# RS485_junction.net
KiCad netlist of a schematic drawn in EAGLE
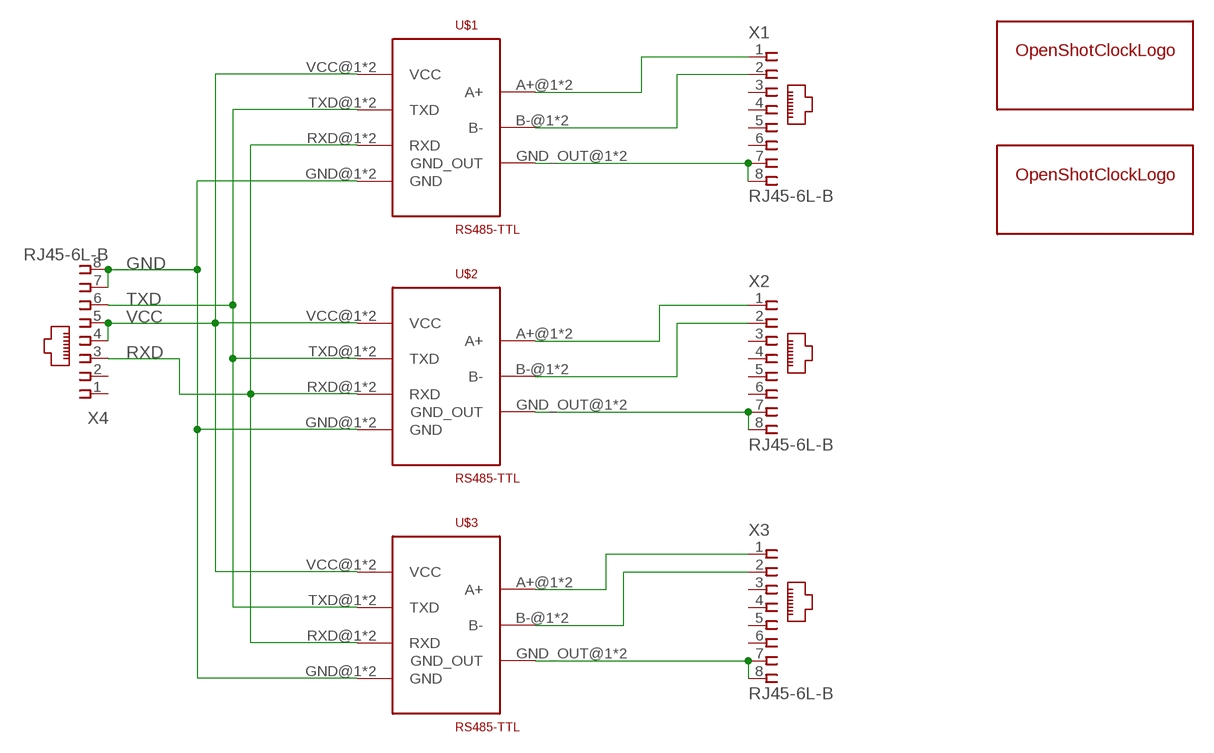
[diagram p0: schematic, sheet 1]

(export (version "E")
  (design (tool "Eeschema 10.0.6"))
  (components
    (comp (ref "U$1")
      (value "RS485-TTL")
      (footprint "eagle-import:RS485-TTL")
      (libsource (lib "eagle-import") (part "RS485-TTL"))
    )
    (comp (ref "U$2")
      (value "RS485-TTL")
      (footprint "eagle-import:RS485-TTL")
      (libsource (lib "eagle-import") (part "RS485-TTL"))
    )
    (comp (ref "U$3")
      (value "RS485-TTL")
      (footprint "eagle-import:RS485-TTL")
      (libsource (lib "eagle-import") (part "RS485-TTL"))
    )
    (comp (ref "U$4")
      (value "OPEN-SHOT-CLOCK-LOGOOSCL-SMALL")
      (footprint "eagle-import:OPEN-SHOT-CLOCK-LOGO-SMALL")
      (libsource (lib "eagle-import") (part "OPEN-SHOT-CLOCK-LOGOOSCL-SMALL"))
    )
    (comp (ref "U$5")
      (value "OPEN-SHOT-CLOCK-LOGOOSCL-H50MM")
      (footprint "eagle-import:OPEN-SHOT-CLOCK-LOGO-H50MM")
      (libsource (lib "eagle-import") (part "OPEN-SHOT-CLOCK-LOGOOSCL-H50MM"))
    )
    (comp (ref "X1")
      (value "RJ45-6L-B")
      (footprint "eagle-import:RJ45-NO-SHIELD")
      (libsource (lib "eagle-import") (part "RJ45-6L-B"))
    )
    (comp (ref "X2")
      (value "RJ45-6L-B")
      (footprint "eagle-import:RJ45-NO-SHIELD")
      (libsource (lib "eagle-import") (part "RJ45-6L-B"))
    )
    (comp (ref "X3")
      (value "RJ45-6L-B")
      (footprint "eagle-import:RJ45-NO-SHIELD")
      (libsource (lib "eagle-import") (part "RJ45-6L-B"))
    )
    (comp (ref "X4")
      (value "RJ45-6L-B")
      (footprint "eagle-import:RJ45-NO-SHIELD")
      (libsource (lib "eagle-import") (part "RJ45-6L-B"))
    )
  )
  (nets
    (net (code "1") (name "/GND") (class "Default")
      (node (ref "U$1") (pin "GND@1") (pinfunction "GND_GND@1") (pintype "bidirectional"))
      (node (ref "U$1") (pin "GND@2") (pinfunction "GND_GND@2") (pintype "bidirectional"))
      (node (ref "U$2") (pin "GND@1") (pinfunction "GND_GND@1") (pintype "bidirectional"))
      (node (ref "U$2") (pin "GND@2") (pinfunction "GND_GND@2") (pintype "bidirectional"))
      (node (ref "U$3") (pin "GND@1") (pinfunction "GND_GND@1") (pintype "bidirectional"))
      (node (ref "U$3") (pin "GND@2") (pinfunction "GND_GND@2") (pintype "bidirectional"))
      (node (ref "X4") (pin "7") (pinfunction "7_7") (pintype "passive"))
      (node (ref "X4") (pin "8") (pinfunction "8_8") (pintype "passive"))
    )
    (net (code "2") (name "/RXD") (class "Default")
      (node (ref "U$1") (pin "RXD@1") (pinfunction "RXD_RXD@1") (pintype "bidirectional"))
      (node (ref "U$1") (pin "RXD@2") (pinfunction "RXD_RXD@2") (pintype "bidirectional"))
      (node (ref "U$2") (pin "RXD@1") (pinfunction "RXD_RXD@1") (pintype "bidirectional"))
      (node (ref "U$2") (pin "RXD@2") (pinfunction "RXD_RXD@2") (pintype "bidirectional"))
      (node (ref "U$3") (pin "RXD@1") (pinfunction "RXD_RXD@1") (pintype "bidirectional"))
      (node (ref "U$3") (pin "RXD@2") (pinfunction "RXD_RXD@2") (pintype "bidirectional"))
      (node (ref "X4") (pin "3") (pinfunction "3_3") (pintype "passive"))
    )
    (net (code "3") (name "/TXD") (class "Default")
      (node (ref "U$1") (pin "TXD@1") (pinfunction "TXD_TXD@1") (pintype "bidirectional"))
      (node (ref "U$1") (pin "TXD@2") (pinfunction "TXD_TXD@2") (pintype "bidirectional"))
      (node (ref "U$2") (pin "TXD@1") (pinfunction "TXD_TXD@1") (pintype "bidirectional"))
      (node (ref "U$2") (pin "TXD@2") (pinfunction "TXD_TXD@2") (pintype "bidirectional"))
      (node (ref "U$3") (pin "TXD@1") (pinfunction "TXD_TXD@1") (pintype "bidirectional"))
      (node (ref "U$3") (pin "TXD@2") (pinfunction "TXD_TXD@2") (pintype "bidirectional"))
      (node (ref "X4") (pin "6") (pinfunction "6_6") (pintype "passive"))
    )
    (net (code "4") (name "/VCC") (class "Default")
      (node (ref "U$1") (pin "VCC@1") (pinfunction "VCC_VCC@1") (pintype "bidirectional"))
      (node (ref "U$1") (pin "VCC@2") (pinfunction "VCC_VCC@2") (pintype "bidirectional"))
      (node (ref "U$2") (pin "VCC@1") (pinfunction "VCC_VCC@1") (pintype "bidirectional"))
      (node (ref "U$2") (pin "VCC@2") (pinfunction "VCC_VCC@2") (pintype "bidirectional"))
      (node (ref "U$3") (pin "VCC@1") (pinfunction "VCC_VCC@1") (pintype "bidirectional"))
      (node (ref "U$3") (pin "VCC@2") (pinfunction "VCC_VCC@2") (pintype "bidirectional"))
      (node (ref "X4") (pin "4") (pinfunction "4_4") (pintype "passive"))
      (node (ref "X4") (pin "5") (pinfunction "5_5") (pintype "passive"))
    )
    (net (code "5") (name "Net-(U$1-A+-PadA+@1)") (class "Default")
      (node (ref "U$1") (pin "A+@1") (pinfunction "A+_A+@1") (pintype "bidirectional"))
      (node (ref "U$1") (pin "A+@2") (pinfunction "A+_A+@2") (pintype "bidirectional"))
      (node (ref "X1") (pin "1") (pinfunction "1_1") (pintype "passive"))
    )
    (net (code "6") (name "Net-(U$1-B--PadB-@1)") (class "Default")
      (node (ref "U$1") (pin "B-@1") (pinfunction "B-_B-@1") (pintype "bidirectional"))
      (node (ref "U$1") (pin "B-@2") (pinfunction "B-_B-@2") (pintype "bidirectional"))
      (node (ref "X1") (pin "2") (pinfunction "2_2") (pintype "passive"))
    )
    (net (code "7") (name "Net-(U$1-GND_OUT-PadGND_OUT@1)") (class "Default")
      (node (ref "U$1") (pin "GND_OUT@1") (pinfunction "GND_OUT_GND_OUT@1") (pintype "bidirectional"))
      (node (ref "U$1") (pin "GND_OUT@2") (pinfunction "GND_OUT_GND_OUT@2") (pintype "bidirectional"))
      (node (ref "X1") (pin "7") (pinfunction "7_7") (pintype "passive"))
      (node (ref "X1") (pin "8") (pinfunction "8_8") (pintype "passive"))
    )
    (net (code "8") (name "Net-(U$2-A+-PadA+@1)") (class "Default")
      (node (ref "U$2") (pin "A+@1") (pinfunction "A+_A+@1") (pintype "bidirectional"))
      (node (ref "U$2") (pin "A+@2") (pinfunction "A+_A+@2") (pintype "bidirectional"))
      (node (ref "X2") (pin "1") (pinfunction "1_1") (pintype "passive"))
    )
    (net (code "9") (name "Net-(U$2-B--PadB-@1)") (class "Default")
      (node (ref "U$2") (pin "B-@1") (pinfunction "B-_B-@1") (pintype "bidirectional"))
      (node (ref "U$2") (pin "B-@2") (pinfunction "B-_B-@2") (pintype "bidirectional"))
      (node (ref "X2") (pin "2") (pinfunction "2_2") (pintype "passive"))
    )
    (net (code "10") (name "Net-(U$2-GND_OUT-PadGND_OUT@1)") (class "Default")
      (node (ref "U$2") (pin "GND_OUT@1") (pinfunction "GND_OUT_GND_OUT@1") (pintype "bidirectional"))
      (node (ref "U$2") (pin "GND_OUT@2") (pinfunction "GND_OUT_GND_OUT@2") (pintype "bidirectional"))
      (node (ref "X2") (pin "7") (pinfunction "7_7") (pintype "passive"))
      (node (ref "X2") (pin "8") (pinfunction "8_8") (pintype "passive"))
    )
    (net (code "11") (name "Net-(U$3-A+-PadA+@1)") (class "Default")
      (node (ref "U$3") (pin "A+@1") (pinfunction "A+_A+@1") (pintype "bidirectional"))
      (node (ref "U$3") (pin "A+@2") (pinfunction "A+_A+@2") (pintype "bidirectional"))
      (node (ref "X3") (pin "1") (pinfunction "1_1") (pintype "passive"))
    )
    (net (code "12") (name "Net-(U$3-B--PadB-@1)") (class "Default")
      (node (ref "U$3") (pin "B-@1") (pinfunction "B-_B-@1") (pintype "bidirectional"))
      (node (ref "U$3") (pin "B-@2") (pinfunction "B-_B-@2") (pintype "bidirectional"))
      (node (ref "X3") (pin "2") (pinfunction "2_2") (pintype "passive"))
    )
    (net (code "13") (name "Net-(U$3-GND_OUT-PadGND_OUT@1)") (class "Default")
      (node (ref "U$3") (pin "GND_OUT@1") (pinfunction "GND_OUT_GND_OUT@1") (pintype "bidirectional"))
      (node (ref "U$3") (pin "GND_OUT@2") (pinfunction "GND_OUT_GND_OUT@2") (pintype "bidirectional"))
      (node (ref "X3") (pin "7") (pinfunction "7_7") (pintype "passive"))
      (node (ref "X3") (pin "8") (pinfunction "8_8") (pintype "passive"))
    )
    (net (code "14") (name "unconnected-(X1-Pad3)") (class "Default")
      (node (ref "X1") (pin "3") (pinfunction "3_3") (pintype "passive"))
    )
    (net (code "15") (name "unconnected-(X1-Pad4)") (class "Default")
      (node (ref "X1") (pin "4") (pinfunction "4_4") (pintype "passive"))
    )
    (net (code "16") (name "unconnected-(X1-Pad5)") (class "Default")
      (node (ref "X1") (pin "5") (pinfunction "5_5") (pintype "passive"))
    )
    (net (code "17") (name "unconnected-(X1-Pad6)") (class "Default")
      (node (ref "X1") (pin "6") (pinfunction "6_6") (pintype "passive"))
    )
    (net (code "18") (name "unconnected-(X2-Pad3)") (class "Default")
      (node (ref "X2") (pin "3") (pinfunction "3_3") (pintype "passive"))
    )
    (net (code "19") (name "unconnected-(X2-Pad4)") (class "Default")
      (node (ref "X2") (pin "4") (pinfunction "4_4") (pintype "passive"))
    )
    (net (code "20") (name "unconnected-(X2-Pad5)") (class "Default")
      (node (ref "X2") (pin "5") (pinfunction "5_5") (pintype "passive"))
    )
    (net (code "21") (name "unconnected-(X2-Pad6)") (class "Default")
      (node (ref "X2") (pin "6") (pinfunction "6_6") (pintype "passive"))
    )
    (net (code "22") (name "unconnected-(X3-Pad3)") (class "Default")
      (node (ref "X3") (pin "3") (pinfunction "3_3") (pintype "passive"))
    )
    (net (code "23") (name "unconnected-(X3-Pad4)") (class "Default")
      (node (ref "X3") (pin "4") (pinfunction "4_4") (pintype "passive"))
    )
    (net (code "24") (name "unconnected-(X3-Pad5)") (class "Default")
      (node (ref "X3") (pin "5") (pinfunction "5_5") (pintype "passive"))
    )
    (net (code "25") (name "unconnected-(X3-Pad6)") (class "Default")
      (node (ref "X3") (pin "6") (pinfunction "6_6") (pintype "passive"))
    )
    (net (code "26") (name "unconnected-(X4-Pad1)") (class "Default")
      (node (ref "X4") (pin "1") (pinfunction "1_1") (pintype "passive"))
    )
    (net (code "27") (name "unconnected-(X4-Pad2)") (class "Default")
      (node (ref "X4") (pin "2") (pinfunction "2_2") (pintype "passive"))
    )
  )
)
